# EYIC_AD1.net
KiCad netlist of a schematic drawn in EAGLE
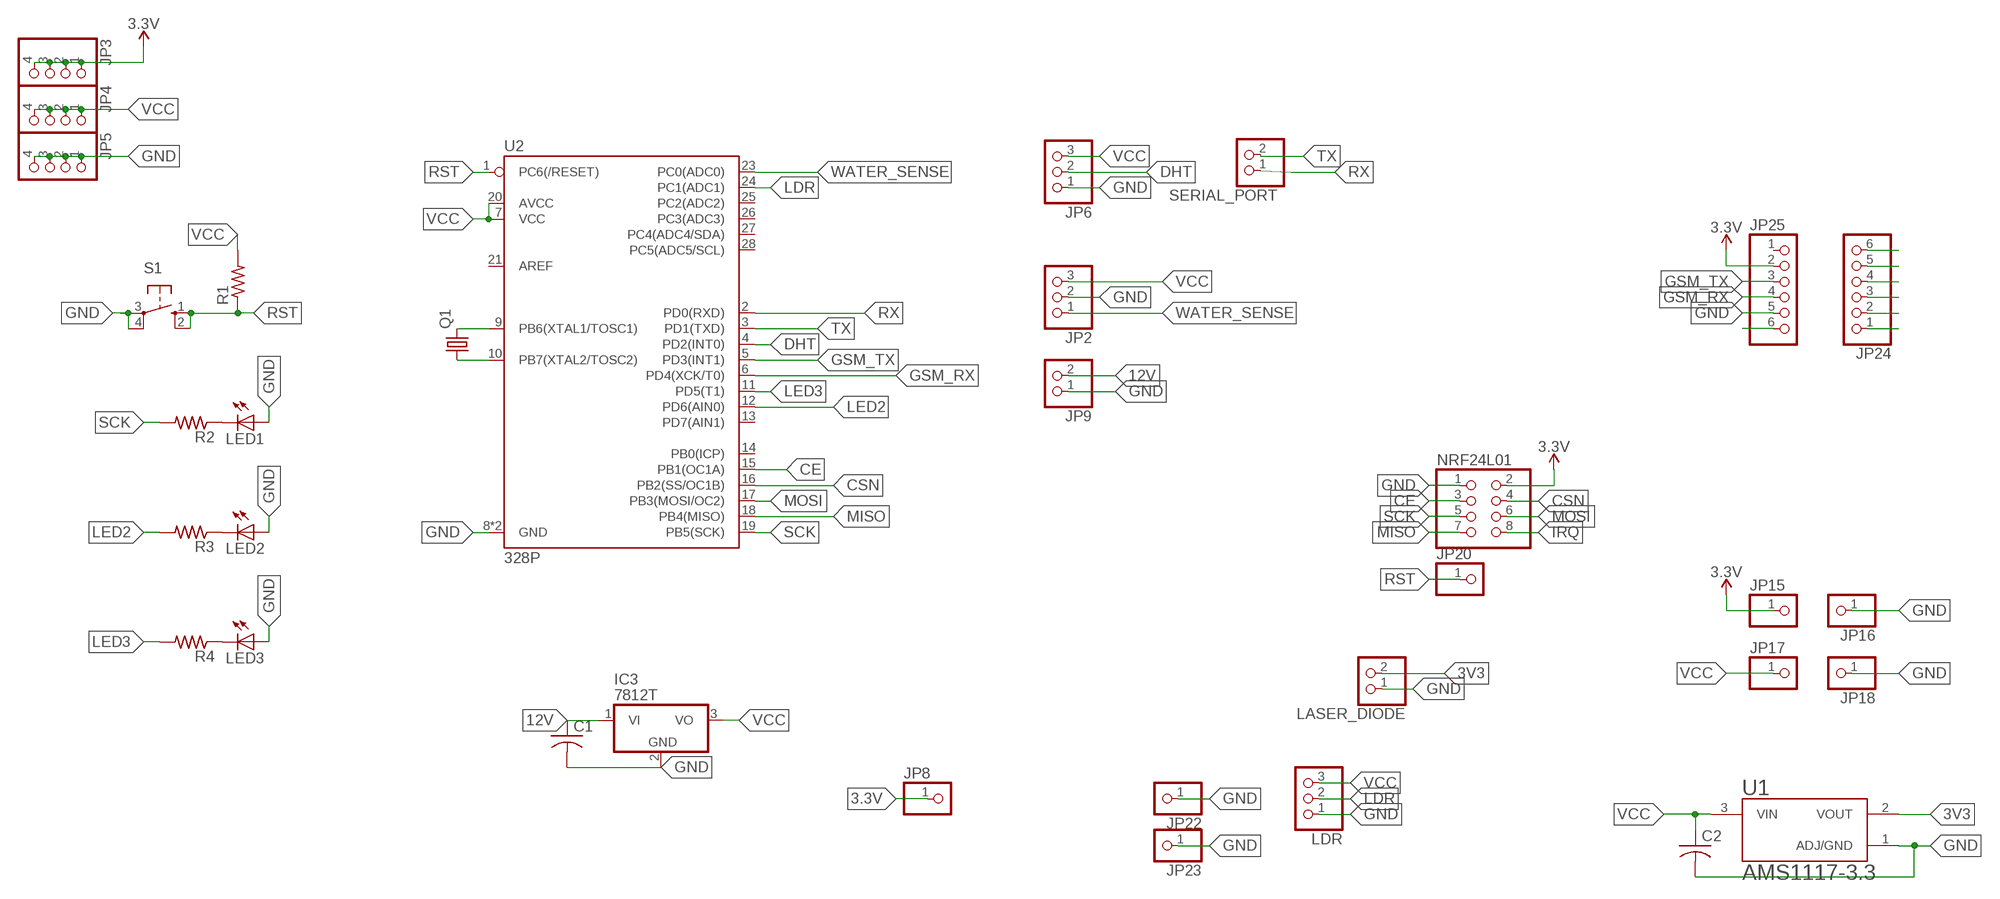
[diagram p0: schematic, sheet 1]

(export (version "E")
  (design (tool "Eeschema 10.0.6"))
  (components
    (comp (ref "C1")
      (value "C-US050-035X075")
      (footprint "eagle-import:C050-035X075")
      (libsource (lib "eagle-import") (part "C-US050-035X075"))
    )
    (comp (ref "C2")
      (value "C-US025-060X050")
      (footprint "eagle-import:C025-060X050")
      (libsource (lib "eagle-import") (part "C-US025-060X050"))
    )
    (comp (ref "IC3")
      (value "7812T")
      (footprint "eagle-import:TO220H")
      (libsource (lib "eagle-import") (part "78T12"))
    )
    (comp (ref "JP2")
      (value "PINHD-1X3")
      (footprint "eagle-import:1X03")
      (libsource (lib "eagle-import") (part "PINHD-1X3"))
    )
    (comp (ref "JP3")
      (value "PINHD-1X4")
      (footprint "eagle-import:1X04")
      (libsource (lib "eagle-import") (part "PINHD-1X4"))
    )
    (comp (ref "JP4")
      (value "PINHD-1X4")
      (footprint "eagle-import:1X04")
      (libsource (lib "eagle-import") (part "PINHD-1X4"))
    )
    (comp (ref "JP5")
      (value "PINHD-1X4")
      (footprint "eagle-import:1X04")
      (libsource (lib "eagle-import") (part "PINHD-1X4"))
    )
    (comp (ref "JP6")
      (value "PINHD-1X3")
      (footprint "eagle-import:1X03")
      (libsource (lib "eagle-import") (part "PINHD-1X3"))
    )
    (comp (ref "JP8")
      (value "PINHD-1X1")
      (footprint "eagle-import:1X01")
      (libsource (lib "eagle-import") (part "PINHD-1X1"))
    )
    (comp (ref "JP9")
      (value "PINHD-1X2")
      (footprint "eagle-import:1X02")
      (libsource (lib "eagle-import") (part "PINHD-1X2"))
    )
    (comp (ref "JP15")
      (value "PINHD-1X1")
      (footprint "eagle-import:1X01")
      (libsource (lib "eagle-import") (part "PINHD-1X1"))
    )
    (comp (ref "JP16")
      (value "PINHD-1X1")
      (footprint "eagle-import:1X01")
      (libsource (lib "eagle-import") (part "PINHD-1X1"))
    )
    (comp (ref "JP17")
      (value "PINHD-1X1")
      (footprint "eagle-import:1X01")
      (libsource (lib "eagle-import") (part "PINHD-1X1"))
    )
    (comp (ref "JP18")
      (value "PINHD-1X1")
      (footprint "eagle-import:1X01")
      (libsource (lib "eagle-import") (part "PINHD-1X1"))
    )
    (comp (ref "JP20")
      (value "PINHD-1X1")
      (footprint "eagle-import:1X01")
      (libsource (lib "eagle-import") (part "PINHD-1X1"))
    )
    (comp (ref "JP22")
      (value "PINHD-1X1")
      (footprint "eagle-import:1X01")
      (libsource (lib "eagle-import") (part "PINHD-1X1"))
    )
    (comp (ref "JP23")
      (value "PINHD-1X1")
      (footprint "eagle-import:1X01")
      (libsource (lib "eagle-import") (part "PINHD-1X1"))
    )
    (comp (ref "JP24")
      (value "PINHD-1X6")
      (footprint "eagle-import:1X06")
      (fields (field (name "SPICEPREFIX") "X"))
      (libsource (lib "eagle-import") (part "PINHD-1X6"))
    )
    (comp (ref "JP25")
      (value "PINHD-1X6")
      (footprint "eagle-import:1X06")
      (fields (field (name "SPICEPREFIX") "X"))
      (libsource (lib "eagle-import") (part "PINHD-1X6"))
    )
    (comp (ref "LASER_DIODE")
      (value "PINHD-1X2")
      (footprint "eagle-import:1X02")
      (libsource (lib "eagle-import") (part "PINHD-1X2"))
    )
    (comp (ref "LDR")
      (value "PINHD-1X3")
      (footprint "eagle-import:1X03")
      (libsource (lib "eagle-import") (part "PINHD-1X3"))
    )
    (comp (ref "LED1")
      (value "LED5MM")
      (footprint "eagle-import:LED5MM")
      (libsource (lib "eagle-import") (part "LED5MM"))
    )
    (comp (ref "LED2")
      (value "LED5MM")
      (footprint "eagle-import:LED5MM")
      (libsource (lib "eagle-import") (part "LED5MM"))
    )
    (comp (ref "LED3")
      (value "LED5MM")
      (footprint "eagle-import:LED5MM")
      (libsource (lib "eagle-import") (part "LED5MM"))
    )
    (comp (ref "NRF24L01")
      (value "PINHD-2X4")
      (footprint "eagle-import:2X04")
      (libsource (lib "eagle-import") (part "PINHD-2X4"))
    )
    (comp (ref "Q1")
      (value "CRYSTALHC49S")
      (footprint "eagle-import:HC49_S")
      (libsource (lib "eagle-import") (part "CRYSTALHC49S"))
    )
    (comp (ref "R1")
      (value "R-US_0207/7")
      (footprint "eagle-import:0207_7")
      (libsource (lib "eagle-import") (part "R-US_0207/7"))
    )
    (comp (ref "R2")
      (value "R-US_0207/7")
      (footprint "eagle-import:0207_7")
      (libsource (lib "eagle-import") (part "R-US_0207/7"))
    )
    (comp (ref "R3")
      (value "R-US_0207/7")
      (footprint "eagle-import:0207_7")
      (libsource (lib "eagle-import") (part "R-US_0207/7"))
    )
    (comp (ref "R4")
      (value "R-US_0207/7")
      (footprint "eagle-import:0207_7")
      (libsource (lib "eagle-import") (part "R-US_0207/7"))
    )
    (comp (ref "S1")
      (value "10-XX")
      (footprint "eagle-import:B3F-10XX")
      (fields (field (name "MPN") "B3F-1000"))
      (libsource (lib "eagle-import") (part "10-XX"))
    )
    (comp (ref "SERIAL_PORT")
      (value "PINHD-1X2")
      (footprint "eagle-import:1X02")
      (libsource (lib "eagle-import") (part "PINHD-1X2"))
    )
    (comp (ref "U1")
      (value "AMS1117-3.3")
      (footprint "eagle-import:SOT229P700X180-4N")
      (fields (field (name "MF") "Advanced Monolithic Systems"))
      (libsource (lib "eagle-import") (part "AMS1117-3.3"))
    )
    (comp (ref "U2")
      (value "328P")
      (footprint "eagle-import:DIP28")
      (libsource (lib "eagle-import") (part "ATMEGA328P_PDIP"))
    )
  )
  (nets
    (net (code "1") (name "3.3V") (class "Default")
      (node (ref "JP15") (pin "1") (pinfunction "1_1") (pintype "passive"))
      (node (ref "JP25") (pin "2") (pinfunction "2_2") (pintype "passive"))
      (node (ref "JP3") (pin "1") (pinfunction "1_1") (pintype "passive"))
      (node (ref "JP3") (pin "2") (pinfunction "2_2") (pintype "passive"))
      (node (ref "JP3") (pin "3") (pinfunction "3_3") (pintype "passive"))
      (node (ref "JP3") (pin "4") (pinfunction "4_4") (pintype "passive"))
      (node (ref "JP8") (pin "1") (pinfunction "1_1") (pintype "passive"))
      (node (ref "NRF24L01") (pin "2") (pinfunction "2_2") (pintype "passive"))
    )
    (net (code "2") (name "3V3") (class "Default")
      (node (ref "LASER_DIODE") (pin "2") (pinfunction "2_2") (pintype "passive"))
      (node (ref "U1") (pin "2") (pinfunction "VOUT_2") (pintype "output"))
    )
    (net (code "3") (name "12V") (class "Default")
      (node (ref "C1") (pin "1") (pinfunction "1_1") (pintype "passive"))
      (node (ref "IC3") (pin "1") (pinfunction "VI_1") (pintype "input"))
      (node (ref "JP9") (pin "2") (pinfunction "2_2") (pintype "passive"))
    )
    (net (code "4") (name "CE") (class "Default")
      (node (ref "NRF24L01") (pin "3") (pinfunction "3_3") (pintype "passive"))
      (node (ref "U2") (pin "15") (pinfunction "PB1(OC1A)_15") (pintype "bidirectional"))
    )
    (net (code "5") (name "CSN") (class "Default")
      (node (ref "NRF24L01") (pin "4") (pinfunction "4_4") (pintype "passive"))
      (node (ref "U2") (pin "16") (pinfunction "PB2(SS/OC1B)_16") (pintype "bidirectional"))
    )
    (net (code "6") (name "DHT") (class "Default")
      (node (ref "JP6") (pin "2") (pinfunction "2_2") (pintype "passive"))
      (node (ref "U2") (pin "4") (pinfunction "PD2(INT0)_4") (pintype "bidirectional"))
    )
    (net (code "7") (name "GND") (class "Default")
      (node (ref "C1") (pin "2") (pinfunction "2_2") (pintype "passive"))
      (node (ref "C2") (pin "2") (pinfunction "2_2") (pintype "passive"))
      (node (ref "IC3") (pin "2") (pinfunction "GND_2") (pintype "passive"))
      (node (ref "JP16") (pin "1") (pinfunction "1_1") (pintype "passive"))
      (node (ref "JP18") (pin "1") (pinfunction "1_1") (pintype "passive"))
      (node (ref "JP2") (pin "2") (pinfunction "2_2") (pintype "passive"))
      (node (ref "JP22") (pin "1") (pinfunction "1_1") (pintype "passive"))
      (node (ref "JP23") (pin "1") (pinfunction "1_1") (pintype "passive"))
      (node (ref "JP25") (pin "5") (pinfunction "5_5") (pintype "passive"))
      (node (ref "JP5") (pin "1") (pinfunction "1_1") (pintype "passive"))
      (node (ref "JP5") (pin "2") (pinfunction "2_2") (pintype "passive"))
      (node (ref "JP5") (pin "3") (pinfunction "3_3") (pintype "passive"))
      (node (ref "JP5") (pin "4") (pinfunction "4_4") (pintype "passive"))
      (node (ref "JP6") (pin "1") (pinfunction "1_1") (pintype "passive"))
      (node (ref "JP9") (pin "1") (pinfunction "1_1") (pintype "passive"))
      (node (ref "LASER_DIODE") (pin "1") (pinfunction "1_1") (pintype "passive"))
      (node (ref "LDR") (pin "1") (pinfunction "1_1") (pintype "passive"))
      (node (ref "LED1") (pin "A") (pinfunction "A_A") (pintype "passive"))
      (node (ref "LED2") (pin "A") (pinfunction "A_A") (pintype "passive"))
      (node (ref "LED3") (pin "A") (pinfunction "A_A") (pintype "passive"))
      (node (ref "NRF24L01") (pin "1") (pinfunction "1_1") (pintype "passive"))
      (node (ref "S1") (pin "3") (pinfunction "P_3") (pintype "passive"))
      (node (ref "S1") (pin "4") (pinfunction "P1_4") (pintype "passive"))
      (node (ref "U1") (pin "1") (pinfunction "ADJ/GND_1") (pintype "power_in"))
      (node (ref "U2") (pin "22") (pinfunction "GND_22") (pintype "bidirectional"))
      (node (ref "U2") (pin "8") (pinfunction "GND_8") (pintype "bidirectional"))
    )
    (net (code "8") (name "GSM_RX") (class "Default")
      (node (ref "JP25") (pin "4") (pinfunction "4_4") (pintype "passive"))
      (node (ref "U2") (pin "6") (pinfunction "PD4(XCK/T0)_6") (pintype "bidirectional"))
    )
    (net (code "9") (name "GSM_TX") (class "Default")
      (node (ref "JP25") (pin "3") (pinfunction "3_3") (pintype "passive"))
      (node (ref "U2") (pin "5") (pinfunction "PD3(INT1)_5") (pintype "bidirectional"))
    )
    (net (code "10") (name "IRQ") (class "Default")
      (node (ref "NRF24L01") (pin "8") (pinfunction "8_8") (pintype "passive"))
    )
    (net (code "11") (name "LDR") (class "Default")
      (node (ref "LDR") (pin "2") (pinfunction "2_2") (pintype "passive"))
      (node (ref "U2") (pin "24") (pinfunction "PC1(ADC1)_24") (pintype "bidirectional"))
    )
    (net (code "12") (name "LED2") (class "Default")
      (node (ref "R3") (pin "2") (pinfunction "2_2") (pintype "passive"))
      (node (ref "U2") (pin "12") (pinfunction "PD6(AIN0)_12") (pintype "bidirectional"))
    )
    (net (code "13") (name "LED3") (class "Default")
      (node (ref "R4") (pin "2") (pinfunction "2_2") (pintype "passive"))
      (node (ref "U2") (pin "11") (pinfunction "PD5(T1)_11") (pintype "bidirectional"))
    )
    (net (code "14") (name "MISO") (class "Default")
      (node (ref "NRF24L01") (pin "7") (pinfunction "7_7") (pintype "passive"))
      (node (ref "U2") (pin "18") (pinfunction "PB4(MISO)_18") (pintype "bidirectional"))
    )
    (net (code "15") (name "MOSI") (class "Default")
      (node (ref "NRF24L01") (pin "6") (pinfunction "6_6") (pintype "passive"))
      (node (ref "U2") (pin "17") (pinfunction "PB3(MOSI/OC2)_17") (pintype "bidirectional"))
    )
    (net (code "16") (name "Net-(LED1-C)") (class "Default")
      (node (ref "LED1") (pin "K") (pinfunction "C_K") (pintype "passive"))
      (node (ref "R2") (pin "1") (pinfunction "1_1") (pintype "passive"))
    )
    (net (code "17") (name "Net-(LED2-C)") (class "Default")
      (node (ref "LED2") (pin "K") (pinfunction "C_K") (pintype "passive"))
      (node (ref "R3") (pin "1") (pinfunction "1_1") (pintype "passive"))
    )
    (net (code "18") (name "Net-(LED3-C)") (class "Default")
      (node (ref "LED3") (pin "K") (pinfunction "C_K") (pintype "passive"))
      (node (ref "R4") (pin "1") (pinfunction "1_1") (pintype "passive"))
    )
    (net (code "19") (name "Net-(U2-PB6(XTAL1{slash}TOSC1))") (class "Default")
      (node (ref "Q1") (pin "2") (pinfunction "2_2") (pintype "passive"))
      (node (ref "U2") (pin "9") (pinfunction "PB6(XTAL1/TOSC1)_9") (pintype "bidirectional"))
    )
    (net (code "20") (name "Net-(U2-PB7(XTAL2{slash}TOSC2))") (class "Default")
      (node (ref "Q1") (pin "1") (pinfunction "1_1") (pintype "passive"))
      (node (ref "U2") (pin "10") (pinfunction "PB7(XTAL2/TOSC2)_10") (pintype "bidirectional"))
    )
    (net (code "21") (name "RST") (class "Default")
      (node (ref "JP20") (pin "1") (pinfunction "1_1") (pintype "passive"))
      (node (ref "R1") (pin "1") (pinfunction "1_1") (pintype "passive"))
      (node (ref "S1") (pin "1") (pinfunction "S_1") (pintype "passive"))
      (node (ref "S1") (pin "2") (pinfunction "S1_2") (pintype "passive"))
      (node (ref "U2") (pin "1") (pinfunction "PC6(/RESET)_1") (pintype "bidirectional"))
    )
    (net (code "22") (name "RX") (class "Default")
      (node (ref "SERIAL_PORT") (pin "1") (pinfunction "1_1") (pintype "passive"))
      (node (ref "U2") (pin "2") (pinfunction "PD0(RXD)_2") (pintype "bidirectional"))
    )
    (net (code "23") (name "SCK") (class "Default")
      (node (ref "NRF24L01") (pin "5") (pinfunction "5_5") (pintype "passive"))
      (node (ref "R2") (pin "2") (pinfunction "2_2") (pintype "passive"))
      (node (ref "U2") (pin "19") (pinfunction "PB5(SCK)_19") (pintype "bidirectional"))
    )
    (net (code "24") (name "TX") (class "Default")
      (node (ref "SERIAL_PORT") (pin "2") (pinfunction "2_2") (pintype "passive"))
      (node (ref "U2") (pin "3") (pinfunction "PD1(TXD)_3") (pintype "bidirectional"))
    )
    (net (code "25") (name "VCC") (class "Default")
      (node (ref "C2") (pin "1") (pinfunction "1_1") (pintype "passive"))
      (node (ref "IC3") (pin "3") (pinfunction "VO_3") (pintype "passive"))
      (node (ref "JP17") (pin "1") (pinfunction "1_1") (pintype "passive"))
      (node (ref "JP2") (pin "3") (pinfunction "3_3") (pintype "passive"))
      (node (ref "JP4") (pin "1") (pinfunction "1_1") (pintype "passive"))
      (node (ref "JP4") (pin "2") (pinfunction "2_2") (pintype "passive"))
      (node (ref "JP4") (pin "3") (pinfunction "3_3") (pintype "passive"))
      (node (ref "JP4") (pin "4") (pinfunction "4_4") (pintype "passive"))
      (node (ref "JP6") (pin "3") (pinfunction "3_3") (pintype "passive"))
      (node (ref "LDR") (pin "3") (pinfunction "3_3") (pintype "passive"))
      (node (ref "R1") (pin "2") (pinfunction "2_2") (pintype "passive"))
      (node (ref "U1") (pin "3") (pinfunction "VIN_3") (pintype "input"))
      (node (ref "U2") (pin "20") (pinfunction "AVCC_20") (pintype "bidirectional"))
      (node (ref "U2") (pin "7") (pinfunction "VCC_7") (pintype "bidirectional"))
    )
    (net (code "26") (name "WATER_SENSE") (class "Default")
      (node (ref "JP2") (pin "1") (pinfunction "1_1") (pintype "passive"))
      (node (ref "U2") (pin "23") (pinfunction "PC0(ADC0)_23") (pintype "bidirectional"))
    )
    (net (code "27") (name "unconnected-(JP24-Pad1)") (class "Default")
      (node (ref "JP24") (pin "1") (pinfunction "1_1") (pintype "passive"))
    )
    (net (code "28") (name "unconnected-(JP24-Pad2)") (class "Default")
      (node (ref "JP24") (pin "2") (pinfunction "2_2") (pintype "passive"))
    )
    (net (code "29") (name "unconnected-(JP24-Pad3)") (class "Default")
      (node (ref "JP24") (pin "3") (pinfunction "3_3") (pintype "passive"))
    )
    (net (code "30") (name "unconnected-(JP24-Pad4)") (class "Default")
      (node (ref "JP24") (pin "4") (pinfunction "4_4") (pintype "passive"))
    )
    (net (code "31") (name "unconnected-(JP24-Pad5)") (class "Default")
      (node (ref "JP24") (pin "5") (pinfunction "5_5") (pintype "passive"))
    )
    (net (code "32") (name "unconnected-(JP24-Pad6)") (class "Default")
      (node (ref "JP24") (pin "6") (pinfunction "6_6") (pintype "passive"))
    )
    (net (code "33") (name "unconnected-(JP25-Pad1)") (class "Default")
      (node (ref "JP25") (pin "1") (pinfunction "1_1") (pintype "passive"))
    )
    (net (code "34") (name "unconnected-(JP25-Pad6)") (class "Default")
      (node (ref "JP25") (pin "6") (pinfunction "6_6") (pintype "passive"))
    )
    (net (code "35") (name "unconnected-(U2-AREF-Pad21)") (class "Default")
      (node (ref "U2") (pin "21") (pinfunction "AREF_21") (pintype "bidirectional"))
    )
    (net (code "36") (name "unconnected-(U2-PB0(ICP)-Pad14)") (class "Default")
      (node (ref "U2") (pin "14") (pinfunction "PB0(ICP)_14") (pintype "bidirectional"))
    )
    (net (code "37") (name "unconnected-(U2-PC2(ADC2)-Pad25)") (class "Default")
      (node (ref "U2") (pin "25") (pinfunction "PC2(ADC2)_25") (pintype "bidirectional"))
    )
    (net (code "38") (name "unconnected-(U2-PC3(ADC3)-Pad26)") (class "Default")
      (node (ref "U2") (pin "26") (pinfunction "PC3(ADC3)_26") (pintype "bidirectional"))
    )
    (net (code "39") (name "unconnected-(U2-PC4(ADC4{slash}SDA)-Pad27)") (class "Default")
      (node (ref "U2") (pin "27") (pinfunction "PC4(ADC4/SDA)_27") (pintype "bidirectional"))
    )
    (net (code "40") (name "unconnected-(U2-PC5(ADC5{slash}SCL)-Pad28)") (class "Default")
      (node (ref "U2") (pin "28") (pinfunction "PC5(ADC5/SCL)_28") (pintype "bidirectional"))
    )
    (net (code "41") (name "unconnected-(U2-PD7(AIN1)-Pad13)") (class "Default")
      (node (ref "U2") (pin "13") (pinfunction "PD7(AIN1)_13") (pintype "bidirectional"))
    )
  )
)
